# task_3.net
KiCad netlist of a schematic drawn in EAGLE
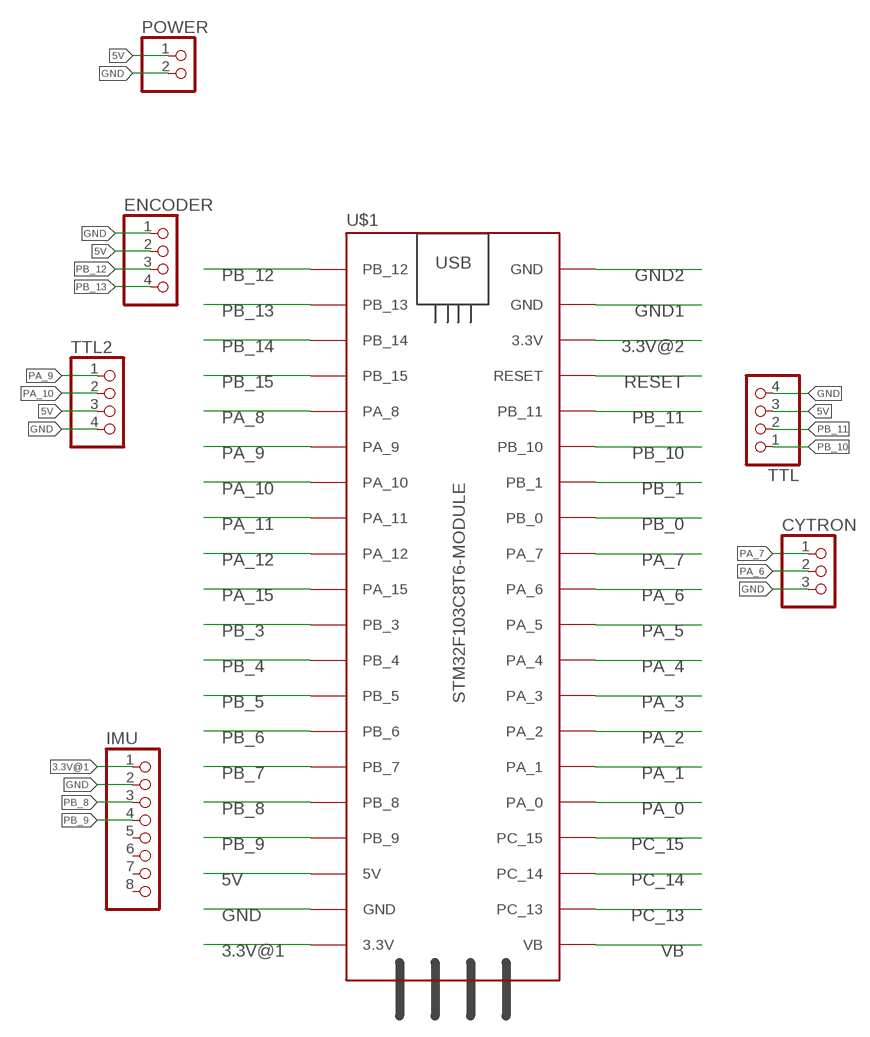
[diagram p0: schematic, sheet 1]

(export (version "E")
  (design (tool "Eeschema 10.0.6"))
  (components
    (comp (ref "CYTRON")
      (value "PINHD-3_DATA")
      (footprint "eagle-import:1X03_DATA")
      (libsource (lib "eagle-import") (part "PINHD-3_DATA"))
    )
    (comp (ref "ENCODER")
      (value "PINHD-4_DATA")
      (footprint "eagle-import:1X04_DATA")
      (libsource (lib "eagle-import") (part "PINHD-4_DATA"))
    )
    (comp (ref "IMU")
      (value "PINHD-1X8")
      (footprint "eagle-import:1X08")
      (libsource (lib "eagle-import") (part "PINHD-1X8"))
    )
    (comp (ref "POWER")
      (value "PINHD-2_DATA")
      (footprint "eagle-import:1X02_DATA")
      (libsource (lib "eagle-import") (part "PINHD-2_DATA"))
    )
    (comp (ref "TTL")
      (value "PINHD-4_DATA")
      (footprint "eagle-import:1X04_DATA")
      (libsource (lib "eagle-import") (part "PINHD-4_DATA"))
    )
    (comp (ref "TTL2")
      (value "PINHD-4_DATA")
      (footprint "eagle-import:1X04_DATA")
      (libsource (lib "eagle-import") (part "PINHD-4_DATA"))
    )
    (comp (ref "U$1")
      (value "STM32F103C8T6-MODULE")
      (footprint "eagle-import:STM32F103C8T6-MODULE")
      (libsource (lib "eagle-import") (part "STM32F103C8T6-MODULE"))
    )
  )
  (nets
    (net (code "1") (name "/3.3V@2") (class "Default")
      (node (ref "U$1") (pin "3.3V_2") (pinfunction "3.3V_3.3V_2") (pintype "bidirectional"))
    )
    (net (code "2") (name "/GND1") (class "Default")
      (node (ref "U$1") (pin "GND_2") (pinfunction "GND_GND_2") (pintype "bidirectional"))
    )
    (net (code "3") (name "/GND2") (class "Default")
      (node (ref "U$1") (pin "GND_3") (pinfunction "GND_GND_3") (pintype "power_in"))
    )
    (net (code "4") (name "/PA_0") (class "Default")
      (node (ref "U$1") (pin "PA_0") (pinfunction "PA_0_PA_0") (pintype "bidirectional"))
    )
    (net (code "5") (name "/PA_1") (class "Default")
      (node (ref "U$1") (pin "PA_1") (pinfunction "PA_1_PA_1") (pintype "bidirectional"))
    )
    (net (code "6") (name "/PA_2") (class "Default")
      (node (ref "U$1") (pin "PA_2") (pinfunction "PA_2_PA_2") (pintype "bidirectional"))
    )
    (net (code "7") (name "/PA_3") (class "Default")
      (node (ref "U$1") (pin "PA_3") (pinfunction "PA_3_PA_3") (pintype "bidirectional"))
    )
    (net (code "8") (name "/PA_4") (class "Default")
      (node (ref "U$1") (pin "PA_4") (pinfunction "PA_4_PA_4") (pintype "bidirectional"))
    )
    (net (code "9") (name "/PA_5") (class "Default")
      (node (ref "U$1") (pin "PA_5") (pinfunction "PA_5_PA_5") (pintype "bidirectional"))
    )
    (net (code "10") (name "/PA_8") (class "Default")
      (node (ref "U$1") (pin "PA_8") (pinfunction "PA_8_PA_8") (pintype "bidirectional"))
    )
    (net (code "11") (name "/PA_11") (class "Default")
      (node (ref "U$1") (pin "PA_11") (pinfunction "PA_11_PA_11") (pintype "bidirectional"))
    )
    (net (code "12") (name "/PA_12") (class "Default")
      (node (ref "U$1") (pin "PA_12") (pinfunction "PA_12_PA_12") (pintype "bidirectional"))
    )
    (net (code "13") (name "/PA_15") (class "Default")
      (node (ref "U$1") (pin "PA_15") (pinfunction "PA_15_PA_15") (pintype "bidirectional"))
    )
    (net (code "14") (name "/PB_0") (class "Default")
      (node (ref "U$1") (pin "PB_0") (pinfunction "PB_0_PB_0") (pintype "bidirectional"))
    )
    (net (code "15") (name "/PB_1") (class "Default")
      (node (ref "U$1") (pin "PB_1") (pinfunction "PB_1_PB_1") (pintype "bidirectional"))
    )
    (net (code "16") (name "/PB_3") (class "Default")
      (node (ref "U$1") (pin "PB_3") (pinfunction "PB_3_PB_3") (pintype "bidirectional"))
    )
    (net (code "17") (name "/PB_4") (class "Default")
      (node (ref "U$1") (pin "PB_4") (pinfunction "PB_4_PB_4") (pintype "bidirectional"))
    )
    (net (code "18") (name "/PB_5") (class "Default")
      (node (ref "U$1") (pin "PB_5") (pinfunction "PB_5_PB_5") (pintype "bidirectional"))
    )
    (net (code "19") (name "/PB_6") (class "Default")
      (node (ref "U$1") (pin "PB_6") (pinfunction "PB_6_PB_6") (pintype "bidirectional"))
    )
    (net (code "20") (name "/PB_7") (class "Default")
      (node (ref "U$1") (pin "PB_7") (pinfunction "PB_7_PB_7") (pintype "bidirectional"))
    )
    (net (code "21") (name "/PB_14") (class "Default")
      (node (ref "U$1") (pin "PB_14") (pinfunction "PB_14_PB_14") (pintype "bidirectional"))
    )
    (net (code "22") (name "/PB_15") (class "Default")
      (node (ref "U$1") (pin "PB_15") (pinfunction "PB_15_PB_15") (pintype "bidirectional"))
    )
    (net (code "23") (name "/PC_13") (class "Default")
      (node (ref "U$1") (pin "PC_13") (pinfunction "PC_13_PC_13") (pintype "bidirectional"))
    )
    (net (code "24") (name "/PC_14") (class "Default")
      (node (ref "U$1") (pin "PC_14") (pinfunction "PC_14_PC_14") (pintype "bidirectional"))
    )
    (net (code "25") (name "/PC_15") (class "Default")
      (node (ref "U$1") (pin "PC_15") (pinfunction "PC_15_PC_15") (pintype "bidirectional"))
    )
    (net (code "26") (name "/RESET") (class "Default")
      (node (ref "U$1") (pin "RESET") (pinfunction "RESET_RESET") (pintype "bidirectional"))
    )
    (net (code "27") (name "/VB") (class "Default")
      (node (ref "U$1") (pin "VB") (pinfunction "VB_VB") (pintype "bidirectional"))
    )
    (net (code "28") (name "3.3V@1") (class "Default")
      (node (ref "IMU") (pin "1") (pinfunction "1_1") (pintype "passive"))
      (node (ref "U$1") (pin "3.3V_1") (pinfunction "3.3V_3.3V_1") (pintype "bidirectional"))
    )
    (net (code "29") (name "5V") (class "Default")
      (node (ref "ENCODER") (pin "2") (pinfunction "2_2") (pintype "passive"))
      (node (ref "POWER") (pin "1") (pinfunction "1_1") (pintype "passive"))
      (node (ref "TTL") (pin "3") (pinfunction "3_3") (pintype "passive"))
      (node (ref "TTL2") (pin "3") (pinfunction "3_3") (pintype "passive"))
      (node (ref "U$1") (pin "5V") (pinfunction "5V_5V") (pintype "bidirectional"))
    )
    (net (code "30") (name "GND") (class "Default")
      (node (ref "CYTRON") (pin "3") (pinfunction "3_3") (pintype "passive"))
      (node (ref "ENCODER") (pin "1") (pinfunction "1_1") (pintype "passive"))
      (node (ref "IMU") (pin "2") (pinfunction "2_2") (pintype "passive"))
      (node (ref "POWER") (pin "2") (pinfunction "2_2") (pintype "passive"))
      (node (ref "TTL") (pin "4") (pinfunction "4_4") (pintype "passive"))
      (node (ref "TTL2") (pin "4") (pinfunction "4_4") (pintype "passive"))
      (node (ref "U$1") (pin "GND_1") (pinfunction "GND_GND_1") (pintype "bidirectional"))
    )
    (net (code "31") (name "PA_6") (class "Default")
      (node (ref "CYTRON") (pin "2") (pinfunction "2_2") (pintype "passive"))
      (node (ref "U$1") (pin "PA_6") (pinfunction "PA_6_PA_6") (pintype "bidirectional"))
    )
    (net (code "32") (name "PA_7") (class "Default")
      (node (ref "CYTRON") (pin "1") (pinfunction "1_1") (pintype "passive"))
      (node (ref "U$1") (pin "PA_7") (pinfunction "PA_7_PA_7") (pintype "bidirectional"))
    )
    (net (code "33") (name "PA_9") (class "Default")
      (node (ref "TTL2") (pin "1") (pinfunction "1_1") (pintype "passive"))
      (node (ref "U$1") (pin "PA_9") (pinfunction "PA_9_PA_9") (pintype "bidirectional"))
    )
    (net (code "34") (name "PA_10") (class "Default")
      (node (ref "TTL2") (pin "2") (pinfunction "2_2") (pintype "passive"))
      (node (ref "U$1") (pin "PA_10") (pinfunction "PA_10_PA_10") (pintype "bidirectional"))
    )
    (net (code "35") (name "PB_8") (class "Default")
      (node (ref "IMU") (pin "3") (pinfunction "3_3") (pintype "passive"))
      (node (ref "U$1") (pin "PB_8") (pinfunction "PB_8_PB_8") (pintype "bidirectional"))
    )
    (net (code "36") (name "PB_9") (class "Default")
      (node (ref "IMU") (pin "4") (pinfunction "4_4") (pintype "passive"))
      (node (ref "U$1") (pin "PB_9") (pinfunction "PB_9_PB_9") (pintype "bidirectional"))
    )
    (net (code "37") (name "PB_10") (class "Default")
      (node (ref "TTL") (pin "1") (pinfunction "1_1") (pintype "passive"))
      (node (ref "U$1") (pin "PB_10") (pinfunction "PB_10_PB_10") (pintype "bidirectional"))
    )
    (net (code "38") (name "PB_11") (class "Default")
      (node (ref "TTL") (pin "2") (pinfunction "2_2") (pintype "passive"))
      (node (ref "U$1") (pin "PB_11") (pinfunction "PB_11_PB_11") (pintype "bidirectional"))
    )
    (net (code "39") (name "PB_12") (class "Default")
      (node (ref "ENCODER") (pin "3") (pinfunction "3_3") (pintype "passive"))
      (node (ref "U$1") (pin "PB_12") (pinfunction "PB_12_PB_12") (pintype "bidirectional"))
    )
    (net (code "40") (name "PB_13") (class "Default")
      (node (ref "ENCODER") (pin "4") (pinfunction "4_4") (pintype "passive"))
      (node (ref "U$1") (pin "PB_13") (pinfunction "PB_13_PB_13") (pintype "bidirectional"))
    )
    (net (code "41") (name "unconnected-(IMU-Pad5)") (class "Default")
      (node (ref "IMU") (pin "5") (pinfunction "5_5") (pintype "passive"))
    )
    (net (code "42") (name "unconnected-(IMU-Pad6)") (class "Default")
      (node (ref "IMU") (pin "6") (pinfunction "6_6") (pintype "passive"))
    )
    (net (code "43") (name "unconnected-(IMU-Pad7)") (class "Default")
      (node (ref "IMU") (pin "7") (pinfunction "7_7") (pintype "passive"))
    )
    (net (code "44") (name "unconnected-(IMU-Pad8)") (class "Default")
      (node (ref "IMU") (pin "8") (pinfunction "8_8") (pintype "passive"))
    )
  )
)
